# Air_Purifier_ESP32C6.net
KiCad netlist of a schematic drawn in EasyEDA Pro
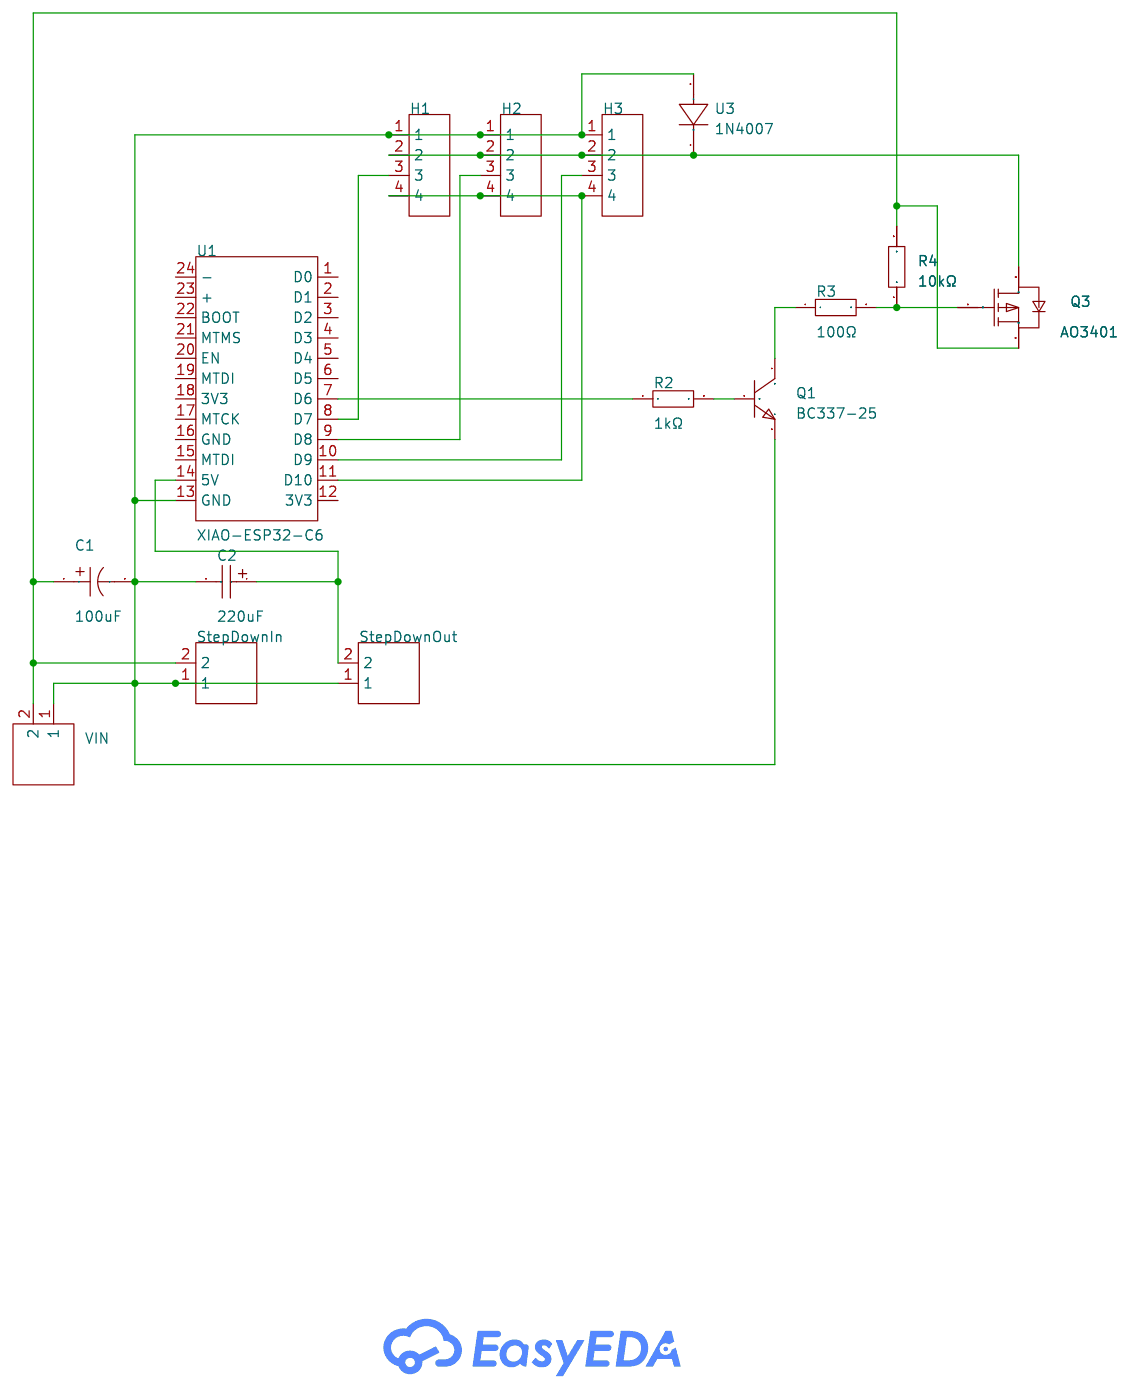
[diagram p0: schematic sheet]

(export (version "E")
  (design (tool "Eeschema 10.0.6"))
  (components
    (comp (ref "C1")
      (value "100uF")
      (footprint "easyedapro:CAP-SMD_BD6.3-L6.6-W6.6-RD")
      (fields (field (name "Manufacturer Part") "8101LDMAA07MH0001T") (field (name "Manufacturer") "FH(风华)"))
      (libsource (lib "easyedapro") (part "8101LDMAA07MH0001T"))
    )
    (comp (ref "C2")
      (value "220uF")
      (footprint "easyedapro:CASE-D_7343")
      (fields (field (name "Manufacturer Part") "TAJD227K010RNJ") (field (name "Manufacturer") "Kyocera AVX"))
      (libsource (lib "easyedapro") (part "TAJD227K010RNJ"))
    )
    (comp (ref "H1")
      (value "~")
      (footprint "easyedapro:HDR-TH_4P-P2.54-V-M")
      (libsource (lib "easyedapro") (part "PZ254V-11-04P"))
    )
    (comp (ref "H2")
      (value "~")
      (footprint "easyedapro:HDR-TH_4P-P2.54-V-M")
      (libsource (lib "easyedapro") (part "PZ254V-11-04P"))
    )
    (comp (ref "H3")
      (value "~")
      (footprint "easyedapro:HDR-TH_4P-P2.54-V-M")
      (libsource (lib "easyedapro") (part "PZ254V-11-04P"))
    )
    (comp (ref "Q1")
      (value "BC337-25")
      (footprint "easyedapro:TO-92-3_L4.9-W3.7-P1.27-L")
      (fields (field (name "Manufacturer") "LGE(鲁光)"))
      (libsource (lib "easyedapro") (part "BC337-25_C713610"))
    )
    (comp (ref "Q3")
      (value "AO3401")
      (footprint "easyedapro:SOT-23-3_L2.9-W1.3-P1.90-LS2.4-BR")
      (fields (field (name "Manufacturer") "YONGYUTAI(永裕泰)"))
      (libsource (lib "easyedapro") (part "AO3401_C6575062"))
    )
    (comp (ref "R2") (value "1kΩ") (footprint "easyedapro:R1206") (libsource (lib "easyedapro") (part "Res")))
    (comp (ref "R3")
      (value "100Ω")
      (footprint "easyedapro:R1206")
      (libsource (lib "easyedapro") (part "Res"))
    )
    (comp (ref "R4")
      (value "10kΩ")
      (footprint "easyedapro:R1206")
      (libsource (lib "easyedapro") (part "Res"))
    )
    (comp (ref "StepDownIn")
      (value "~")
      (footprint "easyedapro:HDR-TH_2P-P2.54-V-M-1")
      (libsource (lib "easyedapro") (part "210S-1*2P L=11.6MMGold-plated black"))
    )
    (comp (ref "StepDownOut")
      (value "~")
      (footprint "easyedapro:HDR-TH_2P-P2.54-V-M-1")
      (libsource (lib "easyedapro") (part "210S-1*2P L=11.6MMGold-plated black"))
    )
    (comp (ref "U1")
      (value "XIAO-ESP32-C6")
      (footprint "easyedapro:LCC-14P_L17.7-W20.8-XIAO-ESP32-C6")
      (libsource (lib "easyedapro") (part "XIAO-ESP32-C6"))
    )
    (comp (ref "U3")
      (value "1N4007")
      (footprint "easyedapro:DO-41_BD2.4-L4.7-P8.70-D0.6-RD")
      (fields (field (name "Manufacturer") "CJ(江苏长电/长晶)"))
      (libsource (lib "easyedapro") (part "1N4007_C5261026"))
    )
    (comp (ref "VIN")
      (value "~")
      (footprint "easyedapro:HDR-TH_2P-P2.54-V-M-1")
      (libsource (lib "easyedapro") (part "210S-1*2P L=11.6MMGold-plated black"))
    )
  )
  (nets
    (net (code "1") (name "Net-(Q1-B)") (class "Default")
      (node (ref "Q1") (pin "2") (pinfunction "B_2") (pintype "input"))
      (node (ref "R2") (pin "2") (pinfunction "2_2") (pintype "input"))
    )
    (net (code "2") (name "Net-(Q1-C)") (class "Default")
      (node (ref "Q1") (pin "1") (pinfunction "C_1") (pintype "input"))
      (node (ref "R3") (pin "1") (pinfunction "1_1") (pintype "input"))
    )
    (net (code "3") (name "Net-(Q1-E)") (class "Default")
      (node (ref "C1") (pin "2") (pinfunction "2_2") (pintype "input"))
      (node (ref "C2") (pin "2") (pinfunction "2_2") (pintype "input"))
      (node (ref "H1") (pin "1") (pinfunction "1_1") (pintype "unspecified"))
      (node (ref "H2") (pin "1") (pinfunction "1_1") (pintype "unspecified"))
      (node (ref "H3") (pin "1") (pinfunction "1_1") (pintype "unspecified"))
      (node (ref "Q1") (pin "3") (pinfunction "E_3") (pintype "input"))
      (node (ref "StepDownIn") (pin "1") (pinfunction "1_1") (pintype "unspecified"))
      (node (ref "StepDownOut") (pin "1") (pinfunction "1_1") (pintype "unspecified"))
      (node (ref "U1") (pin "13") (pinfunction "GND_13") (pintype "unspecified"))
      (node (ref "U3") (pin "2") (pinfunction "A_2") (pintype "unspecified"))
      (node (ref "VIN") (pin "1") (pinfunction "1_1") (pintype "unspecified"))
    )
    (net (code "4") (name "Net-(Q3-D)") (class "Default")
      (node (ref "H1") (pin "2") (pinfunction "2_2") (pintype "unspecified"))
      (node (ref "H2") (pin "2") (pinfunction "2_2") (pintype "unspecified"))
      (node (ref "H3") (pin "2") (pinfunction "2_2") (pintype "unspecified"))
      (node (ref "Q3") (pin "3") (pinfunction "D_3") (pintype "unspecified"))
      (node (ref "U3") (pin "1") (pinfunction "C_1") (pintype "unspecified"))
    )
    (net (code "5") (name "Net-(Q3-G)") (class "Default")
      (node (ref "Q3") (pin "1") (pinfunction "G_1") (pintype "unspecified"))
      (node (ref "R3") (pin "2") (pinfunction "2_2") (pintype "input"))
      (node (ref "R4") (pin "1") (pinfunction "1_1") (pintype "input"))
    )
    (net (code "6") (name "Net-(Q3-S)") (class "Default")
      (node (ref "C1") (pin "1") (pinfunction "1_1") (pintype "input"))
      (node (ref "Q3") (pin "2") (pinfunction "S_2") (pintype "unspecified"))
      (node (ref "R4") (pin "2") (pinfunction "2_2") (pintype "input"))
      (node (ref "StepDownIn") (pin "2") (pinfunction "2_2") (pintype "unspecified"))
      (node (ref "VIN") (pin "2") (pinfunction "2_2") (pintype "unspecified"))
    )
    (net (code "7") (name "Net-(U1-5V)") (class "Default")
      (node (ref "C2") (pin "1") (pinfunction "1_1") (pintype "input"))
      (node (ref "StepDownOut") (pin "2") (pinfunction "2_2") (pintype "unspecified"))
      (node (ref "U1") (pin "14") (pinfunction "5V_14") (pintype "unspecified"))
    )
    (net (code "8") (name "Net-(U1-D6)") (class "Default")
      (node (ref "R2") (pin "1") (pinfunction "1_1") (pintype "input"))
      (node (ref "U1") (pin "7") (pinfunction "D6_7") (pintype "unspecified"))
    )
    (net (code "9") (name "Net-(U1-D7)") (class "Default")
      (node (ref "H1") (pin "3") (pinfunction "3_3") (pintype "unspecified"))
      (node (ref "U1") (pin "8") (pinfunction "D7_8") (pintype "unspecified"))
    )
    (net (code "10") (name "Net-(U1-D8)") (class "Default")
      (node (ref "H2") (pin "3") (pinfunction "3_3") (pintype "unspecified"))
      (node (ref "U1") (pin "9") (pinfunction "D8_9") (pintype "unspecified"))
    )
    (net (code "11") (name "Net-(U1-D9)") (class "Default")
      (node (ref "H3") (pin "3") (pinfunction "3_3") (pintype "unspecified"))
      (node (ref "U1") (pin "10") (pinfunction "D9_10") (pintype "unspecified"))
    )
    (net (code "12") (name "Net-(U1-D10)") (class "Default")
      (node (ref "H1") (pin "4") (pinfunction "4_4") (pintype "unspecified"))
      (node (ref "H2") (pin "4") (pinfunction "4_4") (pintype "unspecified"))
      (node (ref "H3") (pin "4") (pinfunction "4_4") (pintype "unspecified"))
      (node (ref "U1") (pin "11") (pinfunction "D10_11") (pintype "unspecified"))
    )
    (net (code "13") (name "unconnected-(U1-+-Pad23)") (class "Default")
      (node (ref "U1") (pin "23") (pinfunction "+_23") (pintype "unspecified"))
    )
    (net (code "14") (name "unconnected-(U1---Pad24)") (class "Default")
      (node (ref "U1") (pin "24") (pinfunction "-_24") (pintype "unspecified"))
    )
    (net (code "15") (name "unconnected-(U1-3V3-Pad12)") (class "Default")
      (node (ref "U1") (pin "12") (pinfunction "3V3_12") (pintype "unspecified"))
    )
    (net (code "16") (name "unconnected-(U1-3V3-Pad18)") (class "Default")
      (node (ref "U1") (pin "18") (pinfunction "3V3_18") (pintype "unspecified"))
    )
    (net (code "17") (name "unconnected-(U1-BOOT-Pad22)") (class "Default")
      (node (ref "U1") (pin "22") (pinfunction "BOOT_22") (pintype "unspecified"))
    )
    (net (code "18") (name "unconnected-(U1-D0-Pad1)") (class "Default")
      (node (ref "U1") (pin "1") (pinfunction "D0_1") (pintype "unspecified"))
    )
    (net (code "19") (name "unconnected-(U1-D1-Pad2)") (class "Default")
      (node (ref "U1") (pin "2") (pinfunction "D1_2") (pintype "unspecified"))
    )
    (net (code "20") (name "unconnected-(U1-D2-Pad3)") (class "Default")
      (node (ref "U1") (pin "3") (pinfunction "D2_3") (pintype "unspecified"))
    )
    (net (code "21") (name "unconnected-(U1-D3-Pad4)") (class "Default")
      (node (ref "U1") (pin "4") (pinfunction "D3_4") (pintype "unspecified"))
    )
    (net (code "22") (name "unconnected-(U1-D4-Pad5)") (class "Default")
      (node (ref "U1") (pin "5") (pinfunction "D4_5") (pintype "unspecified"))
    )
    (net (code "23") (name "unconnected-(U1-D5-Pad6)") (class "Default")
      (node (ref "U1") (pin "6") (pinfunction "D5_6") (pintype "unspecified"))
    )
    (net (code "24") (name "unconnected-(U1-EN-Pad20)") (class "Default")
      (node (ref "U1") (pin "20") (pinfunction "EN_20") (pintype "unspecified"))
    )
    (net (code "25") (name "unconnected-(U1-GND-Pad16)") (class "Default")
      (node (ref "U1") (pin "16") (pinfunction "GND_16") (pintype "unspecified"))
    )
    (net (code "26") (name "unconnected-(U1-MTCK-Pad17)") (class "Default")
      (node (ref "U1") (pin "17") (pinfunction "MTCK_17") (pintype "unspecified"))
    )
    (net (code "27") (name "unconnected-(U1-MTDI-Pad15)") (class "Default")
      (node (ref "U1") (pin "15") (pinfunction "MTDI_15") (pintype "unspecified"))
    )
    (net (code "28") (name "unconnected-(U1-MTDI-Pad19)") (class "Default")
      (node (ref "U1") (pin "19") (pinfunction "MTDI_19") (pintype "unspecified"))
    )
    (net (code "29") (name "unconnected-(U1-MTMS-Pad21)") (class "Default")
      (node (ref "U1") (pin "21") (pinfunction "MTMS_21") (pintype "unspecified"))
    )
  )
)
